# Solenoids.net
KiCad netlist of a schematic drawn in Altium Designer
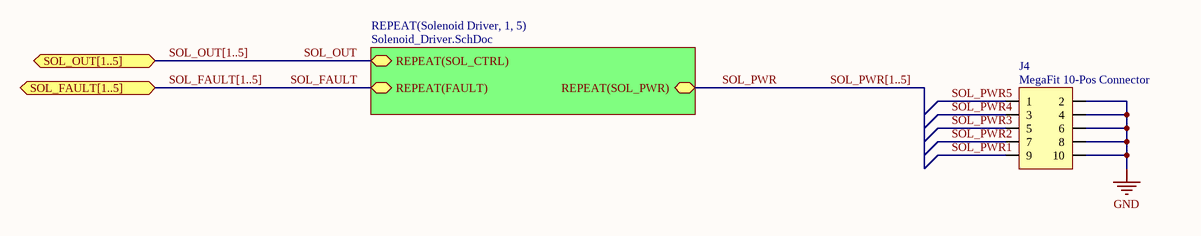
[diagram p0: Solenoids.SchDoc]

(export (version "E")
  (design (tool "Eeschema 10.0.6"))
  (components
    (comp (ref "J4")
      (value "MegaFit 10-Pos Connector")
      (footprint "MegaFit-10Pos")
      (description "Molex MegaFit 10-Pos Connector")
      (libsource (lib "LaunchyRIOComponents") (part "Mega-Fit 10Pos"))
    )
  )
  (nets
    (net (code "16") (name "/SOL_PWR1") (class "Default")
      (node (ref "J4") (pin "9") (pinfunction "9_9") (pintype "passive"))
    )
    (net (code "17") (name "/SOL_PWR2") (class "Default")
      (node (ref "J4") (pin "7") (pinfunction "7_7") (pintype "passive"))
    )
    (net (code "18") (name "/SOL_PWR3") (class "Default")
      (node (ref "J4") (pin "5") (pinfunction "5_5") (pintype "passive"))
    )
    (net (code "19") (name "/SOL_PWR4") (class "Default")
      (node (ref "J4") (pin "3") (pinfunction "3_3") (pintype "passive"))
    )
    (net (code "20") (name "/SOL_PWR5") (class "Default")
      (node (ref "J4") (pin "1") (pinfunction "1_1") (pintype "passive"))
    )
    (net (code "22") (name "GND") (class "Default")
      (node (ref "J4") (pin "10") (pinfunction "10_10") (pintype "passive"))
      (node (ref "J4") (pin "2") (pinfunction "2_2") (pintype "passive"))
      (node (ref "J4") (pin "4") (pinfunction "4_4") (pintype "passive"))
      (node (ref "J4") (pin "6") (pinfunction "6_6") (pintype "passive"))
      (node (ref "J4") (pin "8") (pinfunction "8_8") (pintype "passive"))
    )
  )
)
